# User_Interface.net
KiCad netlist of a schematic drawn in Altium Designer
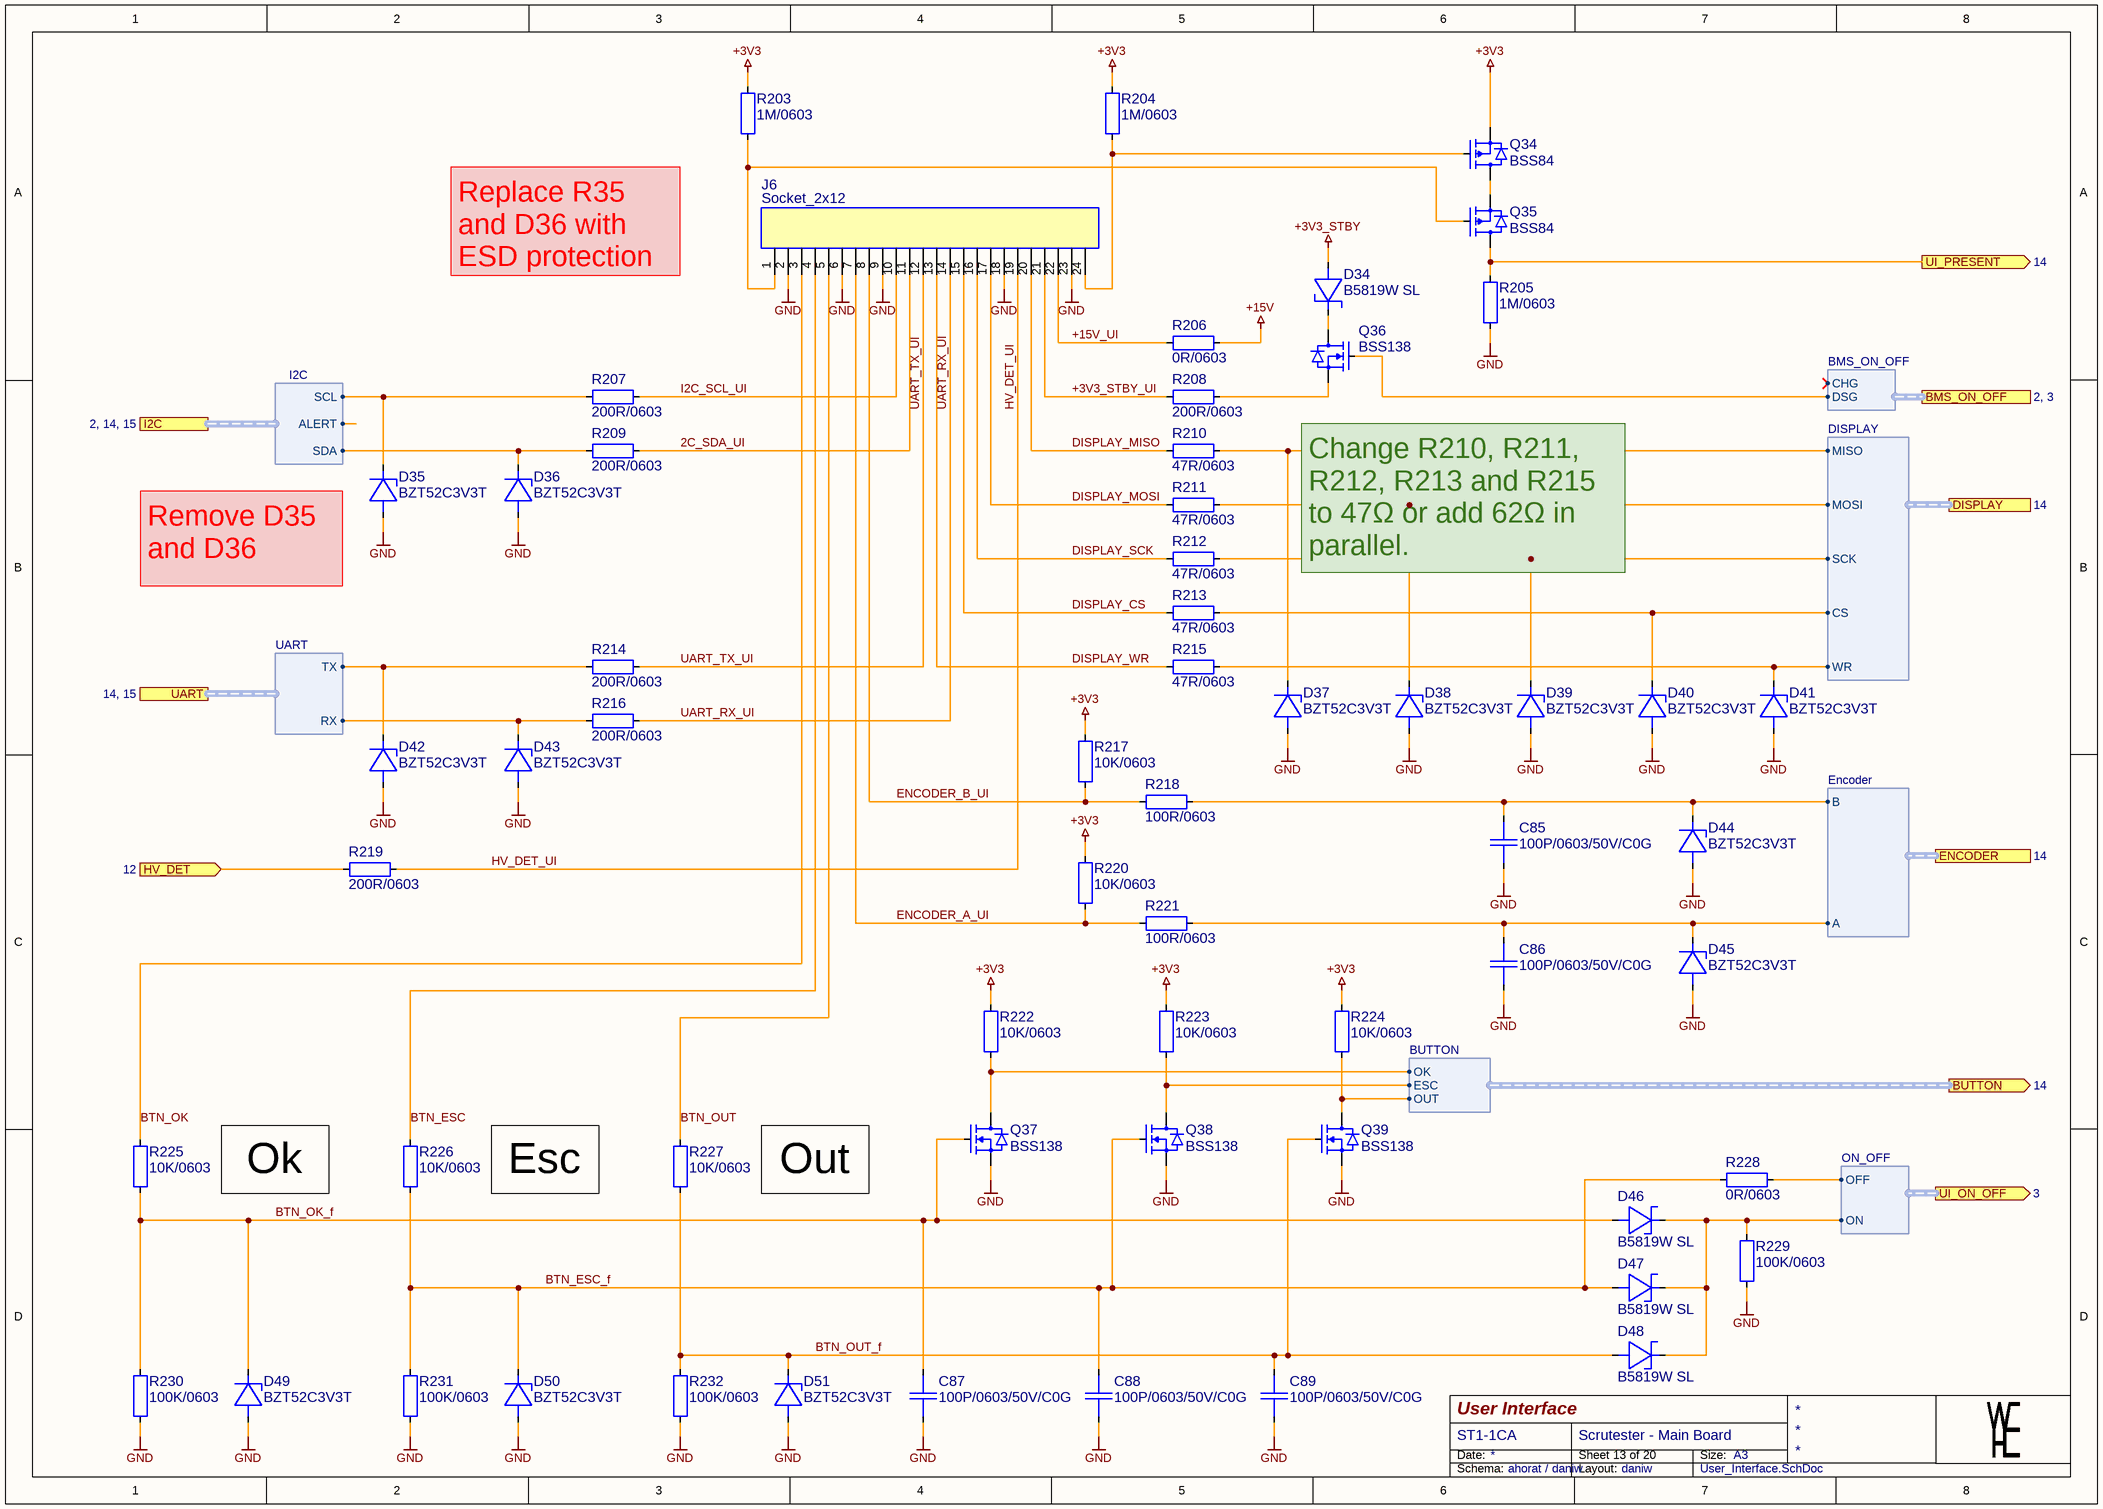
[diagram p0: User_Interface.SchDoc]

(export (version "E")
  (design (tool "Eeschema 10.0.6"))
  (components
    (comp (ref "C85")
      (value "100P/0603/50V/C0G")
      (footprint "CAP0603_C0G")
      (description "CAP SM 0603 100pF 50V C0G")
      (fields (field (name "MANUFACTURER") "GENERIC"))
      (libsource (lib "daniw_altium_lib") (part "C"))
    )
    (comp (ref "C86")
      (value "100P/0603/50V/C0G")
      (footprint "CAP0603_C0G")
      (description "CAP SM 0603 100pF 50V C0G")
      (fields (field (name "MANUFACTURER") "GENERIC"))
      (libsource (lib "daniw_altium_lib") (part "C"))
    )
    (comp (ref "C87")
      (value "100P/0603/50V/C0G")
      (footprint "CAP0603_C0G")
      (description "CAP SM 0603 100pF 50V C0G")
      (fields (field (name "MANUFACTURER") "GENERIC"))
      (libsource (lib "daniw_altium_lib") (part "C"))
    )
    (comp (ref "C88")
      (value "100P/0603/50V/C0G")
      (footprint "CAP0603_C0G")
      (description "CAP SM 0603 100pF 50V C0G")
      (fields (field (name "MANUFACTURER") "GENERIC"))
      (libsource (lib "daniw_altium_lib") (part "C"))
    )
    (comp (ref "C89")
      (value "100P/0603/50V/C0G")
      (footprint "CAP0603_C0G")
      (description "CAP SM 0603 100pF 50V C0G")
      (fields (field (name "MANUFACTURER") "GENERIC"))
      (libsource (lib "daniw_altium_lib") (part "C"))
    )
    (comp (ref "D34")
      (value "B5819W SL")
      (footprint "SOD3718X125")
      (description "40V 600mV@1A 1A SOD-123 Schottky Barrier Diodes")
      (fields (field (name "MANUFACTURER") "GENERIC"))
      (libsource (lib "daniw_altium_lib") (part "D_Schottky"))
    )
    (comp (ref "D35")
      (value "BZT52C3V3T")
      (footprint "SOD1608X065")
      (description "DIODE ZENER 3.3V 300MW SOD523")
      (fields (field (name "MANUFACTURER") "Diodes Incorporated"))
      (libsource (lib "daniw_altium_lib") (part "D_Zener"))
    )
    (comp (ref "D36")
      (value "BZT52C3V3T")
      (footprint "SOD1608X065")
      (description "DIODE ZENER 3.3V 300MW SOD523")
      (fields (field (name "MANUFACTURER") "Diodes Incorporated"))
      (libsource (lib "daniw_altium_lib") (part "D_Zener"))
    )
    (comp (ref "D37")
      (value "BZT52C3V3T")
      (footprint "SOD1608X065")
      (description "DIODE ZENER 3.3V 300MW SOD523")
      (fields (field (name "MANUFACTURER") "Diodes Incorporated"))
      (libsource (lib "daniw_altium_lib") (part "D_Zener"))
    )
    (comp (ref "D38")
      (value "BZT52C3V3T")
      (footprint "SOD1608X065")
      (description "DIODE ZENER 3.3V 300MW SOD523")
      (fields (field (name "MANUFACTURER") "Diodes Incorporated"))
      (libsource (lib "daniw_altium_lib") (part "D_Zener"))
    )
    (comp (ref "D39")
      (value "BZT52C3V3T")
      (footprint "SOD1608X065")
      (description "DIODE ZENER 3.3V 300MW SOD523")
      (fields (field (name "MANUFACTURER") "Diodes Incorporated"))
      (libsource (lib "daniw_altium_lib") (part "D_Zener"))
    )
    (comp (ref "D40")
      (value "BZT52C3V3T")
      (footprint "SOD1608X065")
      (description "DIODE ZENER 3.3V 300MW SOD523")
      (fields (field (name "MANUFACTURER") "Diodes Incorporated"))
      (libsource (lib "daniw_altium_lib") (part "D_Zener"))
    )
    (comp (ref "D41")
      (value "BZT52C3V3T")
      (footprint "SOD1608X065")
      (description "DIODE ZENER 3.3V 300MW SOD523")
      (fields (field (name "MANUFACTURER") "Diodes Incorporated"))
      (libsource (lib "daniw_altium_lib") (part "D_Zener"))
    )
    (comp (ref "D42")
      (value "BZT52C3V3T")
      (footprint "SOD1608X065")
      (description "DIODE ZENER 3.3V 300MW SOD523")
      (fields (field (name "MANUFACTURER") "Diodes Incorporated"))
      (libsource (lib "daniw_altium_lib") (part "D_Zener"))
    )
    (comp (ref "D43")
      (value "BZT52C3V3T")
      (footprint "SOD1608X065")
      (description "DIODE ZENER 3.3V 300MW SOD523")
      (fields (field (name "MANUFACTURER") "Diodes Incorporated"))
      (libsource (lib "daniw_altium_lib") (part "D_Zener"))
    )
    (comp (ref "D44")
      (value "BZT52C3V3T")
      (footprint "SOD1608X065")
      (description "DIODE ZENER 3.3V 300MW SOD523")
      (fields (field (name "MANUFACTURER") "Diodes Incorporated"))
      (libsource (lib "daniw_altium_lib") (part "D_Zener"))
    )
    (comp (ref "D45")
      (value "BZT52C3V3T")
      (footprint "SOD1608X065")
      (description "DIODE ZENER 3.3V 300MW SOD523")
      (fields (field (name "MANUFACTURER") "Diodes Incorporated"))
      (libsource (lib "daniw_altium_lib") (part "D_Zener"))
    )
    (comp (ref "D46")
      (value "B5819W SL")
      (footprint "SOD3718X125")
      (description "40V 600mV@1A 1A SOD-123 Schottky Barrier Diodes")
      (fields (field (name "MANUFACTURER") "GENERIC"))
      (libsource (lib "daniw_altium_lib") (part "D_Schottky"))
    )
    (comp (ref "D47")
      (value "B5819W SL")
      (footprint "SOD3718X125")
      (description "40V 600mV@1A 1A SOD-123 Schottky Barrier Diodes")
      (fields (field (name "MANUFACTURER") "GENERIC"))
      (libsource (lib "daniw_altium_lib") (part "D_Schottky"))
    )
    (comp (ref "D48")
      (value "B5819W SL")
      (footprint "SOD3718X125")
      (description "40V 600mV@1A 1A SOD-123 Schottky Barrier Diodes")
      (fields (field (name "MANUFACTURER") "GENERIC"))
      (libsource (lib "daniw_altium_lib") (part "D_Schottky"))
    )
    (comp (ref "D49")
      (value "BZT52C3V3T")
      (footprint "SOD1608X065")
      (description "DIODE ZENER 3.3V 300MW SOD523")
      (fields (field (name "MANUFACTURER") "Diodes Incorporated"))
      (libsource (lib "daniw_altium_lib") (part "D_Zener"))
    )
    (comp (ref "D50")
      (value "BZT52C3V3T")
      (footprint "SOD1608X065")
      (description "DIODE ZENER 3.3V 300MW SOD523")
      (fields (field (name "MANUFACTURER") "Diodes Incorporated"))
      (libsource (lib "daniw_altium_lib") (part "D_Zener"))
    )
    (comp (ref "D51")
      (value "BZT52C3V3T")
      (footprint "SOD1608X065")
      (description "DIODE ZENER 3.3V 300MW SOD523")
      (fields (field (name "MANUFACTURER") "Diodes Incorporated"))
      (libsource (lib "daniw_altium_lib") (part "D_Zener"))
    )
    (comp (ref "J6")
      (value "Socket_2x12")
      (footprint "SOCK_254_2X12_700")
      (description "Socket 2.100mil 2x12, height 7mm")
      (fields (field (name "PART NUMBER") "Socket_2x12_7mm") (field (name "MANUFACTURER") "GENERIC"))
      (libsource (lib "daniw_altium_lib") (part "CON24"))
    )
    (comp (ref "Q34")
      (value "BSS84")
      (footprint "SOT2395P280X125-3-SE")
      (description "50V P-Channel MOSFET")
      (fields (field (name "MANUFACTURER") "GENERIC"))
      (libsource (lib "daniw_altium_lib") (part "MOSFET_P_G1_D3_S2"))
    )
    (comp (ref "Q35")
      (value "BSS84")
      (footprint "SOT2395P280X125-3-SE")
      (description "50V P-Channel MOSFET")
      (fields (field (name "MANUFACTURER") "GENERIC"))
      (libsource (lib "daniw_altium_lib") (part "MOSFET_P_G1_D3_S2"))
    )
    (comp (ref "Q36")
      (value "BSS138")
      (footprint "SOT2395P280X125-3-SE")
      (description "N-Kanal 50 V 220mA (Ta) 350mW (Ta) Oberflächenmontage SOT-23")
      (fields (field (name "MANUFACTURER") "GENERIC"))
      (libsource (lib "daniw_altium_lib") (part "MOSFET_N_G1_D3_S2"))
    )
    (comp (ref "Q37")
      (value "BSS138")
      (footprint "SOT2395P280X125-3-SE")
      (description "N-Kanal 50 V 220mA (Ta) 350mW (Ta) Oberflächenmontage SOT-23")
      (fields (field (name "MANUFACTURER") "GENERIC"))
      (libsource (lib "daniw_altium_lib") (part "MOSFET_N_G1_D3_S2"))
    )
    (comp (ref "Q38")
      (value "BSS138")
      (footprint "SOT2395P280X125-3-SE")
      (description "N-Kanal 50 V 220mA (Ta) 350mW (Ta) Oberflächenmontage SOT-23")
      (fields (field (name "MANUFACTURER") "GENERIC"))
      (libsource (lib "daniw_altium_lib") (part "MOSFET_N_G1_D3_S2"))
    )
    (comp (ref "Q39")
      (value "BSS138")
      (footprint "SOT2395P280X125-3-SE")
      (description "N-Kanal 50 V 220mA (Ta) 350mW (Ta) Oberflächenmontage SOT-23")
      (fields (field (name "MANUFACTURER") "GENERIC"))
      (libsource (lib "daniw_altium_lib") (part "MOSFET_N_G1_D3_S2"))
    )
    (comp (ref "R203")
      (value "1M/0603")
      (footprint "R0603-0.40-WW")
      (description "RES SM 0603 1M")
      (fields (field (name "MANUFACTURER") "GENERIC"))
      (libsource (lib "daniw_altium_lib") (part "R"))
    )
    (comp (ref "R204")
      (value "1M/0603")
      (footprint "R0603-0.40-WW")
      (description "RES SM 0603 1M")
      (fields (field (name "MANUFACTURER") "GENERIC"))
      (libsource (lib "daniw_altium_lib") (part "R"))
    )
    (comp (ref "R205")
      (value "1M/0603")
      (footprint "R0603-0.40-WW")
      (description "RES SM 0603 1M")
      (fields (field (name "MANUFACTURER") "GENERIC"))
      (libsource (lib "daniw_altium_lib") (part "R"))
    )
    (comp (ref "R206")
      (value "0R/0603")
      (footprint "R0603-0.40-WW")
      (description "RES SM 0603 0R")
      (fields (field (name "MANUFACTURER") "GENERIC"))
      (libsource (lib "daniw_altium_lib") (part "R"))
    )
    (comp (ref "R207")
      (value "200R/0603")
      (footprint "R0603-0.40-WW")
      (description "RES SM 0603 200R")
      (fields (field (name "MANUFACTURER") "GENERIC"))
      (libsource (lib "daniw_altium_lib") (part "R"))
    )
    (comp (ref "R208")
      (value "200R/0603")
      (footprint "R0603-0.40-WW")
      (description "RES SM 0603 200R")
      (fields (field (name "MANUFACTURER") "GENERIC"))
      (libsource (lib "daniw_altium_lib") (part "R"))
    )
    (comp (ref "R209")
      (value "200R/0603")
      (footprint "R0603-0.40-WW")
      (description "RES SM 0603 200R")
      (fields (field (name "MANUFACTURER") "GENERIC"))
      (libsource (lib "daniw_altium_lib") (part "R"))
    )
    (comp (ref "R210")
      (value "47R/0603")
      (footprint "R0603-0.40-WW")
      (description "RES SM 0603 47R")
      (fields (field (name "MANUFACTURER") "GENERIC"))
      (libsource (lib "daniw_altium_lib") (part "R"))
    )
    (comp (ref "R211")
      (value "47R/0603")
      (footprint "R0603-0.40-WW")
      (description "RES SM 0603 47R")
      (fields (field (name "MANUFACTURER") "GENERIC"))
      (libsource (lib "daniw_altium_lib") (part "R"))
    )
    (comp (ref "R212")
      (value "47R/0603")
      (footprint "R0603-0.40-WW")
      (description "RES SM 0603 47R")
      (fields (field (name "MANUFACTURER") "GENERIC"))
      (libsource (lib "daniw_altium_lib") (part "R"))
    )
    (comp (ref "R213")
      (value "47R/0603")
      (footprint "R0603-0.40-WW")
      (description "RES SM 0603 47R")
      (fields (field (name "MANUFACTURER") "GENERIC"))
      (libsource (lib "daniw_altium_lib") (part "R"))
    )
    (comp (ref "R214")
      (value "200R/0603")
      (footprint "R0603-0.40-WW")
      (description "RES SM 0603 200R")
      (fields (field (name "MANUFACTURER") "GENERIC"))
      (libsource (lib "daniw_altium_lib") (part "R"))
    )
    (comp (ref "R215")
      (value "47R/0603")
      (footprint "R0603-0.40-WW")
      (description "RES SM 0603 47R")
      (fields (field (name "MANUFACTURER") "GENERIC"))
      (libsource (lib "daniw_altium_lib") (part "R"))
    )
    (comp (ref "R216")
      (value "200R/0603")
      (footprint "R0603-0.40-WW")
      (description "RES SM 0603 200R")
      (fields (field (name "MANUFACTURER") "GENERIC"))
      (libsource (lib "daniw_altium_lib") (part "R"))
    )
    (comp (ref "R217")
      (value "10K/0603")
      (footprint "R0603-0.40-WW")
      (description "RES SM 0603 10K")
      (fields (field (name "MANUFACTURER") "GENERIC"))
      (libsource (lib "daniw_altium_lib") (part "R"))
    )
    (comp (ref "R218")
      (value "100R/0603")
      (footprint "R0603-0.40-WW")
      (description "RES SM 0603 100R")
      (fields (field (name "MANUFACTURER") "GENERIC"))
      (libsource (lib "daniw_altium_lib") (part "R"))
    )
    (comp (ref "R219")
      (value "200R/0603")
      (footprint "R0603-0.40-WW")
      (description "RES SM 0603 200R")
      (fields (field (name "MANUFACTURER") "GENERIC"))
      (libsource (lib "daniw_altium_lib") (part "R"))
    )
    (comp (ref "R220")
      (value "10K/0603")
      (footprint "R0603-0.40-WW")
      (description "RES SM 0603 10K")
      (fields (field (name "MANUFACTURER") "GENERIC"))
      (libsource (lib "daniw_altium_lib") (part "R"))
    )
    (comp (ref "R221")
      (value "100R/0603")
      (footprint "R0603-0.40-WW")
      (description "RES SM 0603 100R")
      (fields (field (name "MANUFACTURER") "GENERIC"))
      (libsource (lib "daniw_altium_lib") (part "R"))
    )
    (comp (ref "R222")
      (value "10K/0603")
      (footprint "R0603-0.40-WW")
      (description "RES SM 0603 10K")
      (fields (field (name "MANUFACTURER") "GENERIC"))
      (libsource (lib "daniw_altium_lib") (part "R"))
    )
    (comp (ref "R223")
      (value "10K/0603")
      (footprint "R0603-0.40-WW")
      (description "RES SM 0603 10K")
      (fields (field (name "MANUFACTURER") "GENERIC"))
      (libsource (lib "daniw_altium_lib") (part "R"))
    )
    (comp (ref "R224")
      (value "10K/0603")
      (footprint "R0603-0.40-WW")
      (description "RES SM 0603 10K")
      (fields (field (name "MANUFACTURER") "GENERIC"))
      (libsource (lib "daniw_altium_lib") (part "R"))
    )
    (comp (ref "R225")
      (value "10K/0603")
      (footprint "R0603-0.40-WW")
      (description "RES SM 0603 10K")
      (fields (field (name "MANUFACTURER") "GENERIC"))
      (libsource (lib "daniw_altium_lib") (part "R"))
    )
    (comp (ref "R226")
      (value "10K/0603")
      (footprint "R0603-0.40-WW")
      (description "RES SM 0603 10K")
      (fields (field (name "MANUFACTURER") "GENERIC"))
      (libsource (lib "daniw_altium_lib") (part "R"))
    )
    (comp (ref "R227")
      (value "10K/0603")
      (footprint "R0603-0.40-WW")
      (description "RES SM 0603 10K")
      (fields (field (name "MANUFACTURER") "GENERIC"))
      (libsource (lib "daniw_altium_lib") (part "R"))
    )
    (comp (ref "R228")
      (value "0R/0603")
      (footprint "R0603-0.40-WW")
      (description "RES SM 0603 0R")
      (fields (field (name "MANUFACTURER") "GENERIC"))
      (libsource (lib "daniw_altium_lib") (part "R"))
    )
    (comp (ref "R229")
      (value "100K/0603")
      (footprint "R0603-0.40-WW")
      (description "RES SM 0603 100K")
      (fields (field (name "MANUFACTURER") "GENERIC"))
      (libsource (lib "daniw_altium_lib") (part "R"))
    )
    (comp (ref "R230")
      (value "100K/0603")
      (footprint "R0603-0.40-WW")
      (description "RES SM 0603 100K")
      (fields (field (name "MANUFACTURER") "GENERIC"))
      (libsource (lib "daniw_altium_lib") (part "R"))
    )
    (comp (ref "R231")
      (value "100K/0603")
      (footprint "R0603-0.40-WW")
      (description "RES SM 0603 100K")
      (fields (field (name "MANUFACTURER") "GENERIC"))
      (libsource (lib "daniw_altium_lib") (part "R"))
    )
    (comp (ref "R232")
      (value "100K/0603")
      (footprint "R0603-0.40-WW")
      (description "RES SM 0603 100K")
      (fields (field (name "MANUFACTURER") "GENERIC"))
      (libsource (lib "daniw_altium_lib") (part "R"))
    )
  )
  (nets
    (net (code "8") (name "+3V3") (class "Default")
      (node (ref "Q34") (pin "2") (pinfunction "SOURCE_2") (pintype "passive"))
      (node (ref "R203") (pin "1") (pinfunction "1_1") (pintype "passive"))
      (node (ref "R204") (pin "1") (pinfunction "1_1") (pintype "passive"))
      (node (ref "R217") (pin "1") (pinfunction "1_1") (pintype "passive"))
      (node (ref "R220") (pin "1") (pinfunction "1_1") (pintype "passive"))
      (node (ref "R222") (pin "1") (pinfunction "1_1") (pintype "passive"))
      (node (ref "R223") (pin "1") (pinfunction "1_1") (pintype "passive"))
      (node (ref "R224") (pin "1") (pinfunction "1_1") (pintype "passive"))
    )
    (net (code "9") (name "+3V3_STBY") (class "Default")
      (node (ref "D34") (pin "2") (pinfunction "A_2") (pintype "passive"))
    )
    (net (code "10") (name "+15V") (class "Default")
      (node (ref "R206") (pin "2") (pinfunction "2_2") (pintype "passive"))
    )
    (net (code "11") (name "/+3V3_STBY_UI") (class "Default")
      (node (ref "J6") (pin "21") (pintype "passive"))
      (node (ref "R208") (pin "2") (pinfunction "2_2") (pintype "passive"))
    )
    (net (code "12") (name "/+15V_UI") (class "Default")
      (node (ref "J6") (pin "22") (pintype "passive"))
      (node (ref "R206") (pin "1") (pinfunction "1_1") (pintype "passive"))
    )
    (net (code "13") (name "/2C_SDA_UI") (class "Default")
      (node (ref "J6") (pin "11") (pintype "passive"))
      (node (ref "R209") (pin "2") (pinfunction "2_2") (pintype "passive"))
    )
    (net (code "14") (name "/A") (class "Default")
      (node (ref "C86") (pin "1") (pinfunction "1_1") (pintype "passive"))
      (node (ref "D45") (pin "1") (pinfunction "C_1") (pintype "passive"))
      (node (ref "R221") (pin "2") (pinfunction "2_2") (pintype "passive"))
    )
    (net (code "16") (name "/B") (class "Default")
      (node (ref "C85") (pin "1") (pinfunction "1_1") (pintype "passive"))
      (node (ref "D44") (pin "1") (pinfunction "C_1") (pintype "passive"))
      (node (ref "R218") (pin "2") (pinfunction "2_2") (pintype "passive"))
    )
    (net (code "17") (name "/BTN_ESC") (class "Default")
      (node (ref "J6") (pin "4") (pintype "passive"))
      (node (ref "R226") (pin "1") (pinfunction "1_1") (pintype "passive"))
    )
    (net (code "18") (name "/BTN_ESC_f") (class "Default")
      (node (ref "C88") (pin "1") (pinfunction "1_1") (pintype "passive"))
      (node (ref "D47") (pin "2") (pinfunction "A_2") (pintype "passive"))
      (node (ref "D50") (pin "1") (pinfunction "C_1") (pintype "passive"))
      (node (ref "Q38") (pin "1") (pinfunction "GATE_1") (pintype "passive"))
      (node (ref "R226") (pin "2") (pinfunction "2_2") (pintype "passive"))
      (node (ref "R228") (pin "1") (pinfunction "1_1") (pintype "passive"))
      (node (ref "R231") (pin "1") (pinfunction "1_1") (pintype "passive"))
    )
    (net (code "19") (name "/BTN_OK") (class "Default")
      (node (ref "J6") (pin "3") (pintype "passive"))
      (node (ref "R225") (pin "1") (pinfunction "1_1") (pintype "passive"))
    )
    (net (code "20") (name "/BTN_OK_f") (class "Default")
      (node (ref "C87") (pin "1") (pinfunction "1_1") (pintype "passive"))
      (node (ref "D46") (pin "2") (pinfunction "A_2") (pintype "passive"))
      (node (ref "D49") (pin "1") (pinfunction "C_1") (pintype "passive"))
      (node (ref "Q37") (pin "1") (pinfunction "GATE_1") (pintype "passive"))
      (node (ref "R225") (pin "2") (pinfunction "2_2") (pintype "passive"))
      (node (ref "R230") (pin "1") (pinfunction "1_1") (pintype "passive"))
    )
    (net (code "21") (name "/BTN_OUT") (class "Default")
      (node (ref "J6") (pin "5") (pintype "passive"))
      (node (ref "R227") (pin "1") (pinfunction "1_1") (pintype "passive"))
    )
    (net (code "22") (name "/BTN_OUT_f") (class "Default")
      (node (ref "C89") (pin "1") (pinfunction "1_1") (pintype "passive"))
      (node (ref "D48") (pin "2") (pinfunction "A_2") (pintype "passive"))
      (node (ref "D51") (pin "1") (pinfunction "C_1") (pintype "passive"))
      (node (ref "Q39") (pin "1") (pinfunction "GATE_1") (pintype "passive"))
      (node (ref "R227") (pin "2") (pinfunction "2_2") (pintype "passive"))
      (node (ref "R232") (pin "1") (pinfunction "1_1") (pintype "passive"))
    )
    (net (code "23") (name "/CS") (class "Default")
      (node (ref "D40") (pin "1") (pinfunction "C_1") (pintype "passive"))
      (node (ref "R213") (pin "2") (pinfunction "2_2") (pintype "passive"))
    )
    (net (code "24") (name "/DISPLAY_CS") (class "Default")
      (node (ref "J6") (pin "15") (pintype "passive"))
      (node (ref "R213") (pin "1") (pinfunction "1_1") (pintype "passive"))
    )
    (net (code "25") (name "/DISPLAY_MISO") (class "Default")
      (node (ref "J6") (pin "20") (pintype "passive"))
      (node (ref "R210") (pin "1") (pinfunction "1_1") (pintype "passive"))
    )
    (net (code "26") (name "/DISPLAY_MOSI") (class "Default")
      (node (ref "J6") (pin "17") (pintype "passive"))
      (node (ref "R211") (pin "1") (pinfunction "1_1") (pintype "passive"))
    )
    (net (code "27") (name "/DISPLAY_SCK") (class "Default")
      (node (ref "J6") (pin "16") (pintype "passive"))
      (node (ref "R212") (pin "1") (pinfunction "1_1") (pintype "passive"))
    )
    (net (code "28") (name "/DISPLAY_WR") (class "Default")
      (node (ref "J6") (pin "13") (pintype "passive"))
      (node (ref "R215") (pin "1") (pinfunction "1_1") (pintype "passive"))
    )
    (net (code "29") (name "/DSG") (class "Default")
      (node (ref "Q36") (pin "1") (pinfunction "GATE_1") (pintype "passive"))
    )
    (net (code "30") (name "/ENCODER_A_UI") (class "Default")
      (node (ref "J6") (pin "7") (pintype "passive"))
      (node (ref "R220") (pin "2") (pinfunction "2_2") (pintype "passive"))
      (node (ref "R221") (pin "1") (pinfunction "1_1") (pintype "passive"))
    )
    (net (code "31") (name "/ENCODER_B_UI") (class "Default")
      (node (ref "J6") (pin "8") (pintype "passive"))
      (node (ref "R217") (pin "2") (pinfunction "2_2") (pintype "passive"))
      (node (ref "R218") (pin "1") (pinfunction "1_1") (pintype "passive"))
    )
    (net (code "32") (name "/ESC") (class "Default")
      (node (ref "Q38") (pin "3") (pinfunction "DRAIN_3") (pintype "passive"))
      (node (ref "R223") (pin "2") (pinfunction "2_2") (pintype "passive"))
    )
    (net (code "33") (name "/HV_DET") (class "Default")
      (node (ref "R219") (pin "1") (pinfunction "1_1") (pintype "passive"))
    )
    (net (code "34") (name "/HV_DET_UI") (class "Default")
      (node (ref "J6") (pin "19") (pintype "passive"))
      (node (ref "R219") (pin "2") (pinfunction "2_2") (pintype "passive"))
    )
    (net (code "35") (name "/I2C_SCL_UI") (class "Default")
      (node (ref "J6") (pin "10") (pintype "passive"))
      (node (ref "R207") (pin "2") (pinfunction "2_2") (pintype "passive"))
    )
    (net (code "36") (name "/MISO") (class "Default")
      (node (ref "D37") (pin "1") (pinfunction "C_1") (pintype "passive"))
      (node (ref "R210") (pin "2") (pinfunction "2_2") (pintype "passive"))
    )
    (net (code "37") (name "/MOSI") (class "Default")
      (node (ref "D38") (pin "1") (pinfunction "C_1") (pintype "passive"))
      (node (ref "R211") (pin "2") (pinfunction "2_2") (pintype "passive"))
    )
    (net (code "38") (name "/OFF") (class "Default")
      (node (ref "R228") (pin "2") (pinfunction "2_2") (pintype "passive"))
    )
    (net (code "39") (name "/OK") (class "Default")
      (node (ref "Q37") (pin "3") (pinfunction "DRAIN_3") (pintype "passive"))
      (node (ref "R222") (pin "2") (pinfunction "2_2") (pintype "passive"))
    )
    (net (code "40") (name "/ON") (class "Default")
      (node (ref "D46") (pin "1") (pinfunction "C_1") (pintype "passive"))
      (node (ref "D47") (pin "1") (pinfunction "C_1") (pintype "passive"))
      (node (ref "D48") (pin "1") (pinfunction "C_1") (pintype "passive"))
      (node (ref "R229") (pin "1") (pinfunction "1_1") (pintype "passive"))
    )
    (net (code "41") (name "/OUT") (class "Default")
      (node (ref "Q39") (pin "3") (pinfunction "DRAIN_3") (pintype "passive"))
      (node (ref "R224") (pin "2") (pinfunction "2_2") (pintype "passive"))
    )
    (net (code "42") (name "/RX") (class "Default")
      (node (ref "D43") (pin "1") (pinfunction "C_1") (pintype "passive"))
      (node (ref "R216") (pin "1") (pinfunction "1_1") (pintype "passive"))
    )
    (net (code "43") (name "/SCK") (class "Default")
      (node (ref "D39") (pin "1") (pinfunction "C_1") (pintype "passive"))
      (node (ref "R212") (pin "2") (pinfunction "2_2") (pintype "passive"))
    )
    (net (code "44") (name "/SCL") (class "Default")
      (node (ref "D35") (pin "1") (pinfunction "C_1") (pintype "passive"))
      (node (ref "R207") (pin "1") (pinfunction "1_1") (pintype "passive"))
    )
    (net (code "45") (name "/SDA") (class "Default")
      (node (ref "D36") (pin "1") (pinfunction "C_1") (pintype "passive"))
      (node (ref "R209") (pin "1") (pinfunction "1_1") (pintype "passive"))
    )
    (net (code "46") (name "/TX") (class "Default")
      (node (ref "D42") (pin "1") (pinfunction "C_1") (pintype "passive"))
      (node (ref "R214") (pin "1") (pinfunction "1_1") (pintype "passive"))
    )
    (net (code "47") (name "/UART_RX_UI") (class "Default")
      (node (ref "J6") (pin "14") (pintype "passive"))
      (node (ref "R216") (pin "2") (pinfunction "2_2") (pintype "passive"))
    )
    (net (code "48") (name "/UART_TX_UI") (class "Default")
      (node (ref "J6") (pin "12") (pintype "passive"))
      (node (ref "R214") (pin "2") (pinfunction "2_2") (pintype "passive"))
    )
    (net (code "49") (name "/UI_PRESENT") (class "Default")
      (node (ref "Q35") (pin "3") (pinfunction "DRAIN_3") (pintype "passive"))
      (node (ref "R205") (pin "1") (pinfunction "1_1") (pintype "passive"))
    )
    (net (code "50") (name "/WR") (class "Default")
      (node (ref "D41") (pin "1") (pinfunction "C_1") (pintype "passive"))
      (node (ref "R215") (pin "2") (pinfunction "2_2") (pintype "passive"))
    )
    (net (code "58") (name "GND") (class "Default")
      (node (ref "C85") (pin "2") (pinfunction "2_2") (pintype "passive"))
      (node (ref "C86") (pin "2") (pinfunction "2_2") (pintype "passive"))
      (node (ref "C87") (pin "2") (pinfunction "2_2") (pintype "passive"))
      (node (ref "C88") (pin "2") (pinfunction "2_2") (pintype "passive"))
      (node (ref "C89") (pin "2") (pinfunction "2_2") (pintype "passive"))
      (node (ref "D35") (pin "2") (pinfunction "A_2") (pintype "passive"))
      (node (ref "D36") (pin "2") (pinfunction "A_2") (pintype "passive"))
      (node (ref "D37") (pin "2") (pinfunction "A_2") (pintype "passive"))
      (node (ref "D38") (pin "2") (pinfunction "A_2") (pintype "passive"))
      (node (ref "D39") (pin "2") (pinfunction "A_2") (pintype "passive"))
      (node (ref "D40") (pin "2") (pinfunction "A_2") (pintype "passive"))
      (node (ref "D41") (pin "2") (pinfunction "A_2") (pintype "passive"))
      (node (ref "D42") (pin "2") (pinfunction "A_2") (pintype "passive"))
      (node (ref "D43") (pin "2") (pinfunction "A_2") (pintype "passive"))
      (node (ref "D44") (pin "2") (pinfunction "A_2") (pintype "passive"))
      (node (ref "D45") (pin "2") (pinfunction "A_2") (pintype "passive"))
      (node (ref "D49") (pin "2") (pinfunction "A_2") (pintype "passive"))
      (node (ref "D50") (pin "2") (pinfunction "A_2") (pintype "passive"))
      (node (ref "D51") (pin "2") (pinfunction "A_2") (pintype "passive"))
      (node (ref "J6") (pin "18") (pintype "passive"))
      (node (ref "J6") (pin "2") (pintype "passive"))
      (node (ref "J6") (pin "23") (pintype "passive"))
      (node (ref "J6") (pin "6") (pintype "passive"))
      (node (ref "J6") (pin "9") (pintype "passive"))
      (node (ref "Q37") (pin "2") (pinfunction "SOURCE_2") (pintype "passive"))
      (node (ref "Q38") (pin "2") (pinfunction "SOURCE_2") (pintype "passive"))
      (node (ref "Q39") (pin "2") (pinfunction "SOURCE_2") (pintype "passive"))
      (node (ref "R205") (pin "2") (pinfunction "2_2") (pintype "passive"))
      (node (ref "R229") (pin "2") (pinfunction "2_2") (pintype "passive"))
      (node (ref "R230") (pin "2") (pinfunction "2_2") (pintype "passive"))
      (node (ref "R231") (pin "2") (pinfunction "2_2") (pintype "passive"))
      (node (ref "R232") (pin "2") (pinfunction "2_2") (pintype "passive"))
    )
    (net (code "59") (name "Net-(D34-C)") (class "Default")
      (node (ref "D34") (pin "1") (pinfunction "C_1") (pintype "passive"))
      (node (ref "Q36") (pin "3") (pinfunction "DRAIN_3") (pintype "passive"))
    )
    (net (code "60") (name "Net-(Q34-DRAIN)") (class "Default")
      (node (ref "Q34") (pin "3") (pinfunction "DRAIN_3") (pintype "passive"))
      (node (ref "Q35") (pin "2") (pinfunction "SOURCE_2") (pintype "passive"))
    )
    (net (code "61") (name "Net-(Q34-GATE)") (class "Default")
      (node (ref "J6") (pin "24") (pintype "passive"))
      (node (ref "Q34") (pin "1") (pinfunction "GATE_1") (pintype "passive"))
      (node (ref "R204") (pin "2") (pinfunction "2_2") (pintype "passive"))
    )
    (net (code "62") (name "Net-(Q35-GATE)") (class "Default")
      (node (ref "J6") (pin "1") (pintype "passive"))
      (node (ref "Q35") (pin "1") (pinfunction "GATE_1") (pintype "passive"))
      (node (ref "R203") (pin "2") (pinfunction "2_2") (pintype "passive"))
    )
    (net (code "63") (name "Net-(Q36-SOURCE)") (class "Default")
      (node (ref "Q36") (pin "2") (pinfunction "SOURCE_2") (pintype "passive"))
      (node (ref "R208") (pin "1") (pinfunction "1_1") (pintype "passive"))
    )
  )
)
